# SulaMatikV1.net
KiCad netlist of a schematic drawn in EAGLE
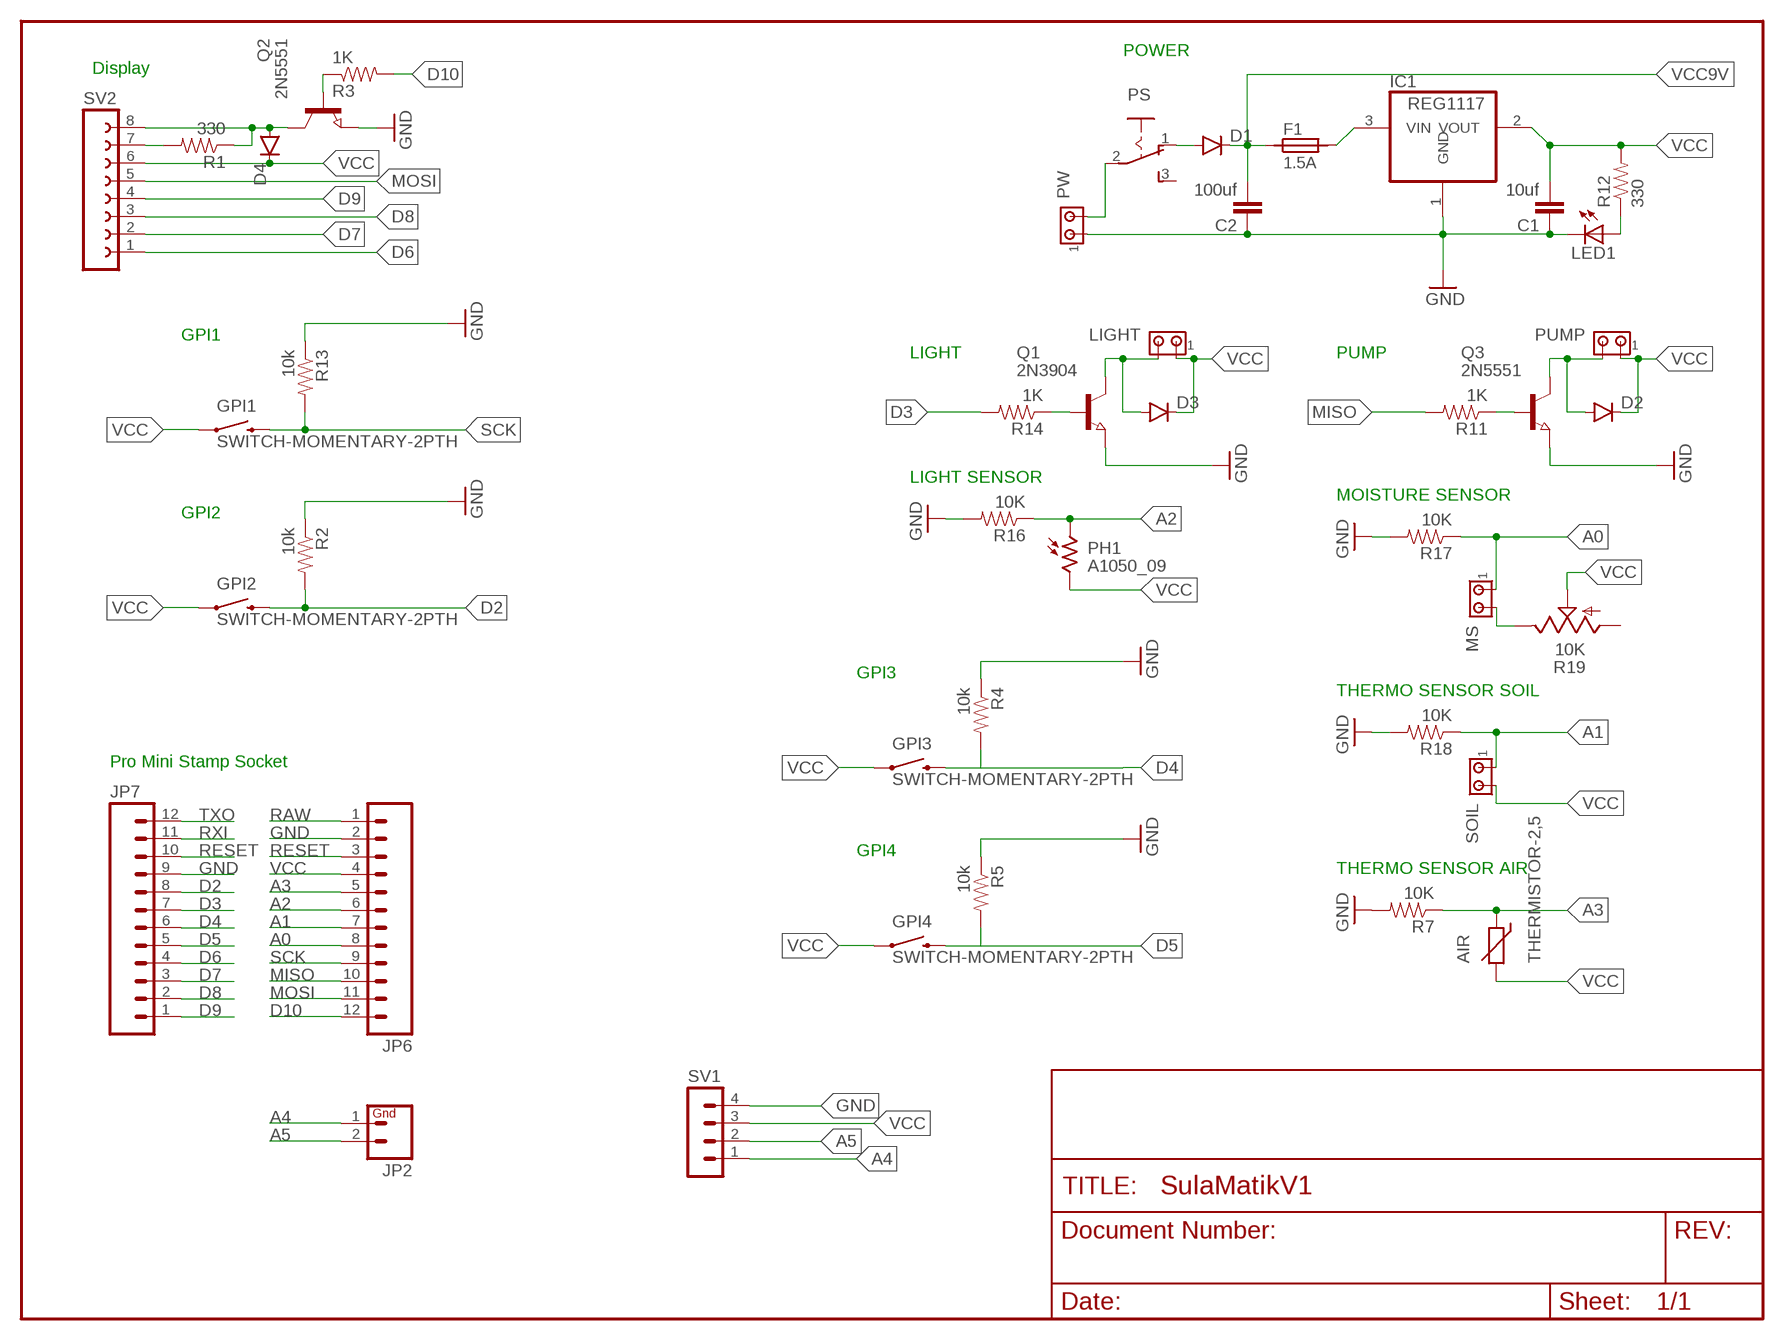
[diagram p0: schematic, sheet 1]

(export (version "E")
  (design (tool "Eeschema 10.0.6"))
  (components
    (comp (ref "AIR")
      (value "THERMISTOR-2,5")
      (footprint "eagle-import:RS-2,5")
      (libsource (lib "eagle-import") (part "THERMISTOR-2,5"))
    )
    (comp (ref "C1")
      (value "10uf")
      (footprint "eagle-import:0805")
      (libsource (lib "eagle-import") (part "CAP0805"))
    )
    (comp (ref "C2")
      (value "100uf")
      (footprint "eagle-import:0805")
      (libsource (lib "eagle-import") (part "CAP0805"))
    )
    (comp (ref "D1")
      (value "DIODESMA")
      (footprint "eagle-import:SMA-DIODE")
      (libsource (lib "eagle-import") (part "DIODESMA"))
    )
    (comp (ref "D2")
      (value "DIODESMA")
      (footprint "eagle-import:SMA-DIODE")
      (libsource (lib "eagle-import") (part "DIODESMA"))
    )
    (comp (ref "D3")
      (value "DIODESMA")
      (footprint "eagle-import:SMA-DIODE")
      (libsource (lib "eagle-import") (part "DIODESMA"))
    )
    (comp (ref "D4")
      (value "DIODESMA")
      (footprint "eagle-import:SMA-DIODE")
      (libsource (lib "eagle-import") (part "DIODESMA"))
    )
    (comp (ref "F1")
      (value "1.5A")
      (footprint "eagle-import:1820")
      (libsource (lib "eagle-import") (part "SIBA194600"))
    )
    (comp (ref "GPI1")
      (value "SWITCH-MOMENTARY-2PTH")
      (footprint "eagle-import:TACTILE-PTH")
      (libsource (lib "eagle-import") (part "SWITCH-MOMENTARY-2PTH"))
    )
    (comp (ref "GPI2")
      (value "SWITCH-MOMENTARY-2PTH")
      (footprint "eagle-import:TACTILE-PTH")
      (libsource (lib "eagle-import") (part "SWITCH-MOMENTARY-2PTH"))
    )
    (comp (ref "GPI3")
      (value "SWITCH-MOMENTARY-2PTH")
      (footprint "eagle-import:TACTILE-PTH")
      (libsource (lib "eagle-import") (part "SWITCH-MOMENTARY-2PTH"))
    )
    (comp (ref "GPI4")
      (value "SWITCH-MOMENTARY-2PTH")
      (footprint "eagle-import:TACTILE-PTH")
      (libsource (lib "eagle-import") (part "SWITCH-MOMENTARY-2PTH"))
    )
    (comp (ref "IC1")
      (value "REG1117")
      (footprint "eagle-import:SOT223")
      (libsource (lib "eagle-import") (part "REG1117"))
    )
    (comp (ref "JP2")
      (value "M02PTH")
      (footprint "eagle-import:1X02")
      (libsource (lib "eagle-import") (part "M02PTH"))
    )
    (comp (ref "JP6")
      (value "M12PTH")
      (footprint "eagle-import:1X12")
      (libsource (lib "eagle-import") (part "M12PTH"))
    )
    (comp (ref "JP7")
      (value "M12PTH")
      (footprint "eagle-import:1X12")
      (libsource (lib "eagle-import") (part "M12PTH"))
    )
    (comp (ref "LED1")
      (value "LEDCHIP-LED0805")
      (footprint "eagle-import:CHIP-LED0805")
      (libsource (lib "eagle-import") (part "LEDCHIP-LED0805"))
    )
    (comp (ref "LIGHT")
      (value "MTA02-100")
      (footprint "eagle-import:10X02MTA")
      (libsource (lib "eagle-import") (part "MTA02-100"))
    )
    (comp (ref "MS")
      (value "MTA02-100")
      (footprint "eagle-import:10X02MTA")
      (libsource (lib "eagle-import") (part "MTA02-100"))
    )
    (comp (ref "PH1")
      (value "A1050_09")
      (footprint "eagle-import:T0-46-A10XX")
      (libsource (lib "eagle-import") (part "A1050_09"))
    )
    (comp (ref "PS")
      (value "255SB")
      (footprint "eagle-import:255SB")
      (libsource (lib "eagle-import") (part "255SB"))
    )
    (comp (ref "PUMP")
      (value "MTA02-100")
      (footprint "eagle-import:10X02MTA")
      (libsource (lib "eagle-import") (part "MTA02-100"))
    )
    (comp (ref "PW")
      (value "MTA02-100")
      (footprint "eagle-import:10X02MTA")
      (libsource (lib "eagle-import") (part "MTA02-100"))
    )
    (comp (ref "Q1")
      (value "2N3904")
      (footprint "eagle-import:SOT23")
      (libsource (lib "eagle-import") (part "NPN-TRANSISTOR_SOT23"))
    )
    (comp (ref "Q2")
      (value "2N5551")
      (footprint "eagle-import:SOT23")
      (libsource (lib "eagle-import") (part "NPN-TRANSISTOR_SOT23"))
    )
    (comp (ref "Q3")
      (value "2N5551")
      (footprint "eagle-import:SOT23")
      (libsource (lib "eagle-import") (part "NPN-TRANSISTOR_SOT23"))
    )
    (comp (ref "R1")
      (value "330")
      (footprint "eagle-import:0805")
      (libsource (lib "eagle-import") (part "RESISTOR0805-RES"))
    )
    (comp (ref "R2")
      (value "10k")
      (footprint "eagle-import:0805")
      (libsource (lib "eagle-import") (part "RESISTOR0805-RES"))
    )
    (comp (ref "R3")
      (value "1K")
      (footprint "eagle-import:0805")
      (libsource (lib "eagle-import") (part "RESISTOR0805-RES"))
    )
    (comp (ref "R4")
      (value "10k")
      (footprint "eagle-import:0805")
      (libsource (lib "eagle-import") (part "RESISTOR0805-RES"))
    )
    (comp (ref "R5")
      (value "10k")
      (footprint "eagle-import:0805")
      (libsource (lib "eagle-import") (part "RESISTOR0805-RES"))
    )
    (comp (ref "R7")
      (value "10K")
      (footprint "eagle-import:0805")
      (libsource (lib "eagle-import") (part "RESISTOR0805-RES"))
    )
    (comp (ref "R11")
      (value "1K")
      (footprint "eagle-import:0805")
      (libsource (lib "eagle-import") (part "RESISTOR0805-RES"))
    )
    (comp (ref "R12")
      (value "330")
      (footprint "eagle-import:0805")
      (libsource (lib "eagle-import") (part "RESISTOR0805-RES"))
    )
    (comp (ref "R13")
      (value "10k")
      (footprint "eagle-import:0805")
      (libsource (lib "eagle-import") (part "RESISTOR0805-RES"))
    )
    (comp (ref "R14")
      (value "1K")
      (footprint "eagle-import:0805")
      (libsource (lib "eagle-import") (part "RESISTOR0805-RES"))
    )
    (comp (ref "R16")
      (value "10K")
      (footprint "eagle-import:0805")
      (libsource (lib "eagle-import") (part "RESISTOR0805-RES"))
    )
    (comp (ref "R17")
      (value "10K")
      (footprint "eagle-import:0805")
      (libsource (lib "eagle-import") (part "RESISTOR0805-RES"))
    )
    (comp (ref "R18")
      (value "10K")
      (footprint "eagle-import:0805")
      (libsource (lib "eagle-import") (part "RESISTOR0805-RES"))
    )
    (comp (ref "R19")
      (value "10K")
      (footprint "eagle-import:CA6V")
      (libsource (lib "eagle-import") (part "TRIM_US-CA6V"))
    )
    (comp (ref "SOIL")
      (value "MTA02-100")
      (footprint "eagle-import:10X02MTA")
      (libsource (lib "eagle-import") (part "MTA02-100"))
    )
    (comp (ref "SV1")
      (value "MA04-1")
      (footprint "eagle-import:MA04-1")
      (libsource (lib "eagle-import") (part "MA04-1"))
    )
    (comp (ref "SV2")
      (value "FE08-1")
      (footprint "eagle-import:FE08")
      (libsource (lib "eagle-import") (part "FE08-1"))
    )
  )
  (nets
    (net (code "1") (name "/RAW") (class "Default")
      (node (ref "JP6") (pin "1") (pinfunction "1_1") (pintype "passive"))
    )
    (net (code "2") (name "/RESET") (class "Default")
      (node (ref "JP6") (pin "3") (pinfunction "3_3") (pintype "passive"))
      (node (ref "JP7") (pin "10") (pinfunction "10_10") (pintype "passive"))
    )
    (net (code "3") (name "/RXI") (class "Default")
      (node (ref "JP7") (pin "11") (pinfunction "11_11") (pintype "passive"))
    )
    (net (code "4") (name "/TXO") (class "Default")
      (node (ref "JP7") (pin "12") (pinfunction "12_12") (pintype "passive"))
    )
    (net (code "5") (name "A0") (class "Default")
      (node (ref "JP6") (pin "8") (pinfunction "8_8") (pintype "passive"))
      (node (ref "MS") (pin "1") (pinfunction "1_1") (pintype "passive"))
      (node (ref "R17") (pin "1") (pinfunction "1_1") (pintype "passive"))
    )
    (net (code "6") (name "A1") (class "Default")
      (node (ref "JP6") (pin "7") (pinfunction "7_7") (pintype "passive"))
      (node (ref "R18") (pin "1") (pinfunction "1_1") (pintype "passive"))
      (node (ref "SOIL") (pin "1") (pinfunction "1_1") (pintype "passive"))
    )
    (net (code "7") (name "A2") (class "Default")
      (node (ref "JP6") (pin "6") (pinfunction "6_6") (pintype "passive"))
      (node (ref "PH1") (pin "1") (pinfunction "1_1") (pintype "passive"))
      (node (ref "R16") (pin "1") (pinfunction "1_1") (pintype "passive"))
    )
    (net (code "8") (name "A3") (class "Default")
      (node (ref "AIR") (pin "1") (pinfunction "1_1") (pintype "passive"))
      (node (ref "JP6") (pin "5") (pinfunction "5_5") (pintype "passive"))
      (node (ref "R7") (pin "1") (pinfunction "1_1") (pintype "passive"))
    )
    (net (code "9") (name "A4") (class "Default")
      (node (ref "JP2") (pin "1") (pinfunction "1_1") (pintype "passive"))
      (node (ref "SV1") (pin "1") (pinfunction "1_1") (pintype "passive"))
    )
    (net (code "10") (name "A5") (class "Default")
      (node (ref "JP2") (pin "2") (pinfunction "2_2") (pintype "passive"))
      (node (ref "SV1") (pin "2") (pinfunction "2_2") (pintype "passive"))
    )
    (net (code "11") (name "D2") (class "Default")
      (node (ref "GPI2") (pin "3") (pinfunction "2_3") (pintype "passive"))
      (node (ref "JP7") (pin "8") (pinfunction "8_8") (pintype "passive"))
      (node (ref "R2") (pin "2") (pinfunction "2_2") (pintype "passive"))
    )
    (net (code "12") (name "D3") (class "Default")
      (node (ref "JP7") (pin "7") (pinfunction "7_7") (pintype "passive"))
      (node (ref "R14") (pin "2") (pinfunction "2_2") (pintype "passive"))
    )
    (net (code "13") (name "D4") (class "Default")
      (node (ref "GPI3") (pin "3") (pinfunction "2_3") (pintype "passive"))
      (node (ref "JP7") (pin "6") (pinfunction "6_6") (pintype "passive"))
      (node (ref "R4") (pin "2") (pinfunction "2_2") (pintype "passive"))
    )
    (net (code "14") (name "D5") (class "Default")
      (node (ref "GPI4") (pin "3") (pinfunction "2_3") (pintype "passive"))
      (node (ref "JP7") (pin "5") (pinfunction "5_5") (pintype "passive"))
      (node (ref "R5") (pin "2") (pinfunction "2_2") (pintype "passive"))
    )
    (net (code "15") (name "D6") (class "Default")
      (node (ref "JP7") (pin "4") (pinfunction "4_4") (pintype "passive"))
      (node (ref "SV2") (pin "1") (pinfunction "1_1") (pintype "passive"))
    )
    (net (code "16") (name "D7") (class "Default")
      (node (ref "JP7") (pin "3") (pinfunction "3_3") (pintype "passive"))
      (node (ref "SV2") (pin "2") (pinfunction "2_2") (pintype "passive"))
    )
    (net (code "17") (name "D8") (class "Default")
      (node (ref "JP7") (pin "2") (pinfunction "2_2") (pintype "passive"))
      (node (ref "SV2") (pin "3") (pinfunction "3_3") (pintype "passive"))
    )
    (net (code "18") (name "D9") (class "Default")
      (node (ref "JP7") (pin "1") (pinfunction "1_1") (pintype "passive"))
      (node (ref "SV2") (pin "4") (pinfunction "4_4") (pintype "passive"))
    )
    (net (code "19") (name "D10") (class "Default")
      (node (ref "JP6") (pin "12") (pinfunction "12_12") (pintype "passive"))
      (node (ref "R3") (pin "2") (pinfunction "2_2") (pintype "passive"))
    )
    (net (code "20") (name "GND") (class "Default")
      (node (ref "C1") (pin "1") (pinfunction "1_1") (pintype "passive"))
      (node (ref "C2") (pin "1") (pinfunction "1_1") (pintype "passive"))
      (node (ref "IC1") (pin "1") (pinfunction "GND_1") (pintype "power_in"))
      (node (ref "JP6") (pin "2") (pinfunction "2_2") (pintype "passive"))
      (node (ref "JP7") (pin "9") (pinfunction "9_9") (pintype "passive"))
      (node (ref "LED1") (pin "C") (pinfunction "C_C") (pintype "passive"))
      (node (ref "PW") (pin "1") (pinfunction "1_1") (pintype "passive"))
      (node (ref "Q1") (pin "2") (pinfunction "E_2") (pintype "passive"))
      (node (ref "Q2") (pin "2") (pinfunction "E_2") (pintype "passive"))
      (node (ref "Q3") (pin "2") (pinfunction "E_2") (pintype "passive"))
      (node (ref "R13") (pin "1") (pinfunction "1_1") (pintype "passive"))
      (node (ref "R16") (pin "2") (pinfunction "2_2") (pintype "passive"))
      (node (ref "R17") (pin "2") (pinfunction "2_2") (pintype "passive"))
      (node (ref "R18") (pin "2") (pinfunction "2_2") (pintype "passive"))
      (node (ref "R2") (pin "1") (pinfunction "1_1") (pintype "passive"))
      (node (ref "R4") (pin "1") (pinfunction "1_1") (pintype "passive"))
      (node (ref "R5") (pin "1") (pinfunction "1_1") (pintype "passive"))
      (node (ref "R7") (pin "2") (pinfunction "2_2") (pintype "passive"))
      (node (ref "SV1") (pin "4") (pinfunction "4_4") (pintype "passive"))
    )
    (net (code "21") (name "MISO") (class "Default")
      (node (ref "JP6") (pin "10") (pinfunction "10_10") (pintype "passive"))
      (node (ref "R11") (pin "2") (pinfunction "2_2") (pintype "passive"))
    )
    (net (code "22") (name "MOSI") (class "Default")
      (node (ref "JP6") (pin "11") (pinfunction "11_11") (pintype "passive"))
      (node (ref "SV2") (pin "5") (pinfunction "5_5") (pintype "passive"))
    )
    (net (code "23") (name "Net-(IC1-VIN)") (class "Default")
      (node (ref "F1") (pin "2") (pinfunction "2_2") (pintype "passive"))
      (node (ref "IC1") (pin "3") (pinfunction "VIN_3") (pintype "input"))
    )
    (net (code "24") (name "Net-(LED1-PadA)") (class "Default")
      (node (ref "LED1") (pin "A") (pinfunction "A_A") (pintype "passive"))
      (node (ref "R12") (pin "1") (pinfunction "1_1") (pintype "passive"))
    )
    (net (code "25") (name "Net-(MS-Pad2)") (class "Default")
      (node (ref "MS") (pin "2") (pinfunction "2_2") (pintype "passive"))
      (node (ref "R19") (pin "E") (pinfunction "E_E") (pintype "passive"))
    )
    (net (code "26") (name "Net-(PS-O)") (class "Default")
      (node (ref "D1") (pin "A") (pinfunction "A_A") (pintype "passive"))
      (node (ref "PS") (pin "1") (pinfunction "O_1") (pintype "passive"))
    )
    (net (code "27") (name "Net-(PS-P)") (class "Default")
      (node (ref "PS") (pin "2") (pinfunction "P_2") (pintype "passive"))
      (node (ref "PW") (pin "2") (pinfunction "2_2") (pintype "passive"))
    )
    (net (code "28") (name "Net-(Q1-B)") (class "Default")
      (node (ref "Q1") (pin "1") (pinfunction "B_1") (pintype "passive"))
      (node (ref "R14") (pin "1") (pinfunction "1_1") (pintype "passive"))
    )
    (net (code "29") (name "Net-(Q1-C)") (class "Default")
      (node (ref "D3") (pin "A") (pinfunction "A_A") (pintype "passive"))
      (node (ref "LIGHT") (pin "2") (pinfunction "2_2") (pintype "passive"))
      (node (ref "Q1") (pin "3") (pinfunction "C_3") (pintype "passive"))
    )
    (net (code "30") (name "Net-(Q2-B)") (class "Default")
      (node (ref "Q2") (pin "1") (pinfunction "B_1") (pintype "passive"))
      (node (ref "R3") (pin "1") (pinfunction "1_1") (pintype "passive"))
    )
    (net (code "31") (name "Net-(Q2-C)") (class "Default")
      (node (ref "D4") (pin "A") (pinfunction "A_A") (pintype "passive"))
      (node (ref "Q2") (pin "3") (pinfunction "C_3") (pintype "passive"))
      (node (ref "R1") (pin "1") (pinfunction "1_1") (pintype "passive"))
      (node (ref "SV2") (pin "8") (pinfunction "8_8") (pintype "passive"))
    )
    (net (code "32") (name "Net-(Q3-B)") (class "Default")
      (node (ref "Q3") (pin "1") (pinfunction "B_1") (pintype "passive"))
      (node (ref "R11") (pin "1") (pinfunction "1_1") (pintype "passive"))
    )
    (net (code "33") (name "Net-(Q3-C)") (class "Default")
      (node (ref "D2") (pin "A") (pinfunction "A_A") (pintype "passive"))
      (node (ref "PUMP") (pin "2") (pinfunction "2_2") (pintype "passive"))
      (node (ref "Q3") (pin "3") (pinfunction "C_3") (pintype "passive"))
    )
    (net (code "34") (name "Net-(R1-Pad2)") (class "Default")
      (node (ref "R1") (pin "2") (pinfunction "2_2") (pintype "passive"))
      (node (ref "SV2") (pin "7") (pinfunction "7_7") (pintype "passive"))
    )
    (net (code "35") (name "SCK") (class "Default")
      (node (ref "GPI1") (pin "3") (pinfunction "2_3") (pintype "passive"))
      (node (ref "JP6") (pin "9") (pinfunction "9_9") (pintype "passive"))
      (node (ref "R13") (pin "2") (pinfunction "2_2") (pintype "passive"))
    )
    (net (code "36") (name "VCC") (class "Default")
      (node (ref "AIR") (pin "2") (pinfunction "2_2") (pintype "passive"))
      (node (ref "C1") (pin "2") (pinfunction "2_2") (pintype "passive"))
      (node (ref "D2") (pin "C") (pinfunction "C_C") (pintype "passive"))
      (node (ref "D3") (pin "C") (pinfunction "C_C") (pintype "passive"))
      (node (ref "D4") (pin "C") (pinfunction "C_C") (pintype "passive"))
      (node (ref "GPI1") (pin "1") (pinfunction "1_1") (pintype "passive"))
      (node (ref "GPI2") (pin "1") (pinfunction "1_1") (pintype "passive"))
      (node (ref "GPI3") (pin "1") (pinfunction "1_1") (pintype "passive"))
      (node (ref "GPI4") (pin "1") (pinfunction "1_1") (pintype "passive"))
      (node (ref "IC1") (pin "2") (pinfunction "VOUT_2") (pintype "output"))
      (node (ref "JP6") (pin "4") (pinfunction "4_4") (pintype "passive"))
      (node (ref "LIGHT") (pin "1") (pinfunction "1_1") (pintype "passive"))
      (node (ref "PH1") (pin "2") (pinfunction "2_2") (pintype "passive"))
      (node (ref "PUMP") (pin "1") (pinfunction "1_1") (pintype "passive"))
      (node (ref "R12") (pin "2") (pinfunction "2_2") (pintype "passive"))
      (node (ref "R19") (pin "S") (pinfunction "S_S") (pintype "passive"))
      (node (ref "SOIL") (pin "2") (pinfunction "2_2") (pintype "passive"))
      (node (ref "SV1") (pin "3") (pinfunction "3_3") (pintype "passive"))
      (node (ref "SV2") (pin "6") (pinfunction "6_6") (pintype "passive"))
    )
    (net (code "37") (name "VCC9V") (class "Default")
      (node (ref "C2") (pin "2") (pinfunction "2_2") (pintype "passive"))
      (node (ref "D1") (pin "C") (pinfunction "C_C") (pintype "passive"))
      (node (ref "F1") (pin "1") (pinfunction "1_1") (pintype "passive"))
    )
    (net (code "38") (name "unconnected-(PS-S-Pad3)") (class "Default")
      (node (ref "PS") (pin "3") (pinfunction "S_3") (pintype "passive"))
    )
    (net (code "39") (name "unconnected-(R19-PadA)") (class "Default")
      (node (ref "R19") (pin "A") (pinfunction "A_A") (pintype "passive"))
    )
  )
)
